# ACS712.net
KiCad netlist of a schematic drawn in Altium Designer
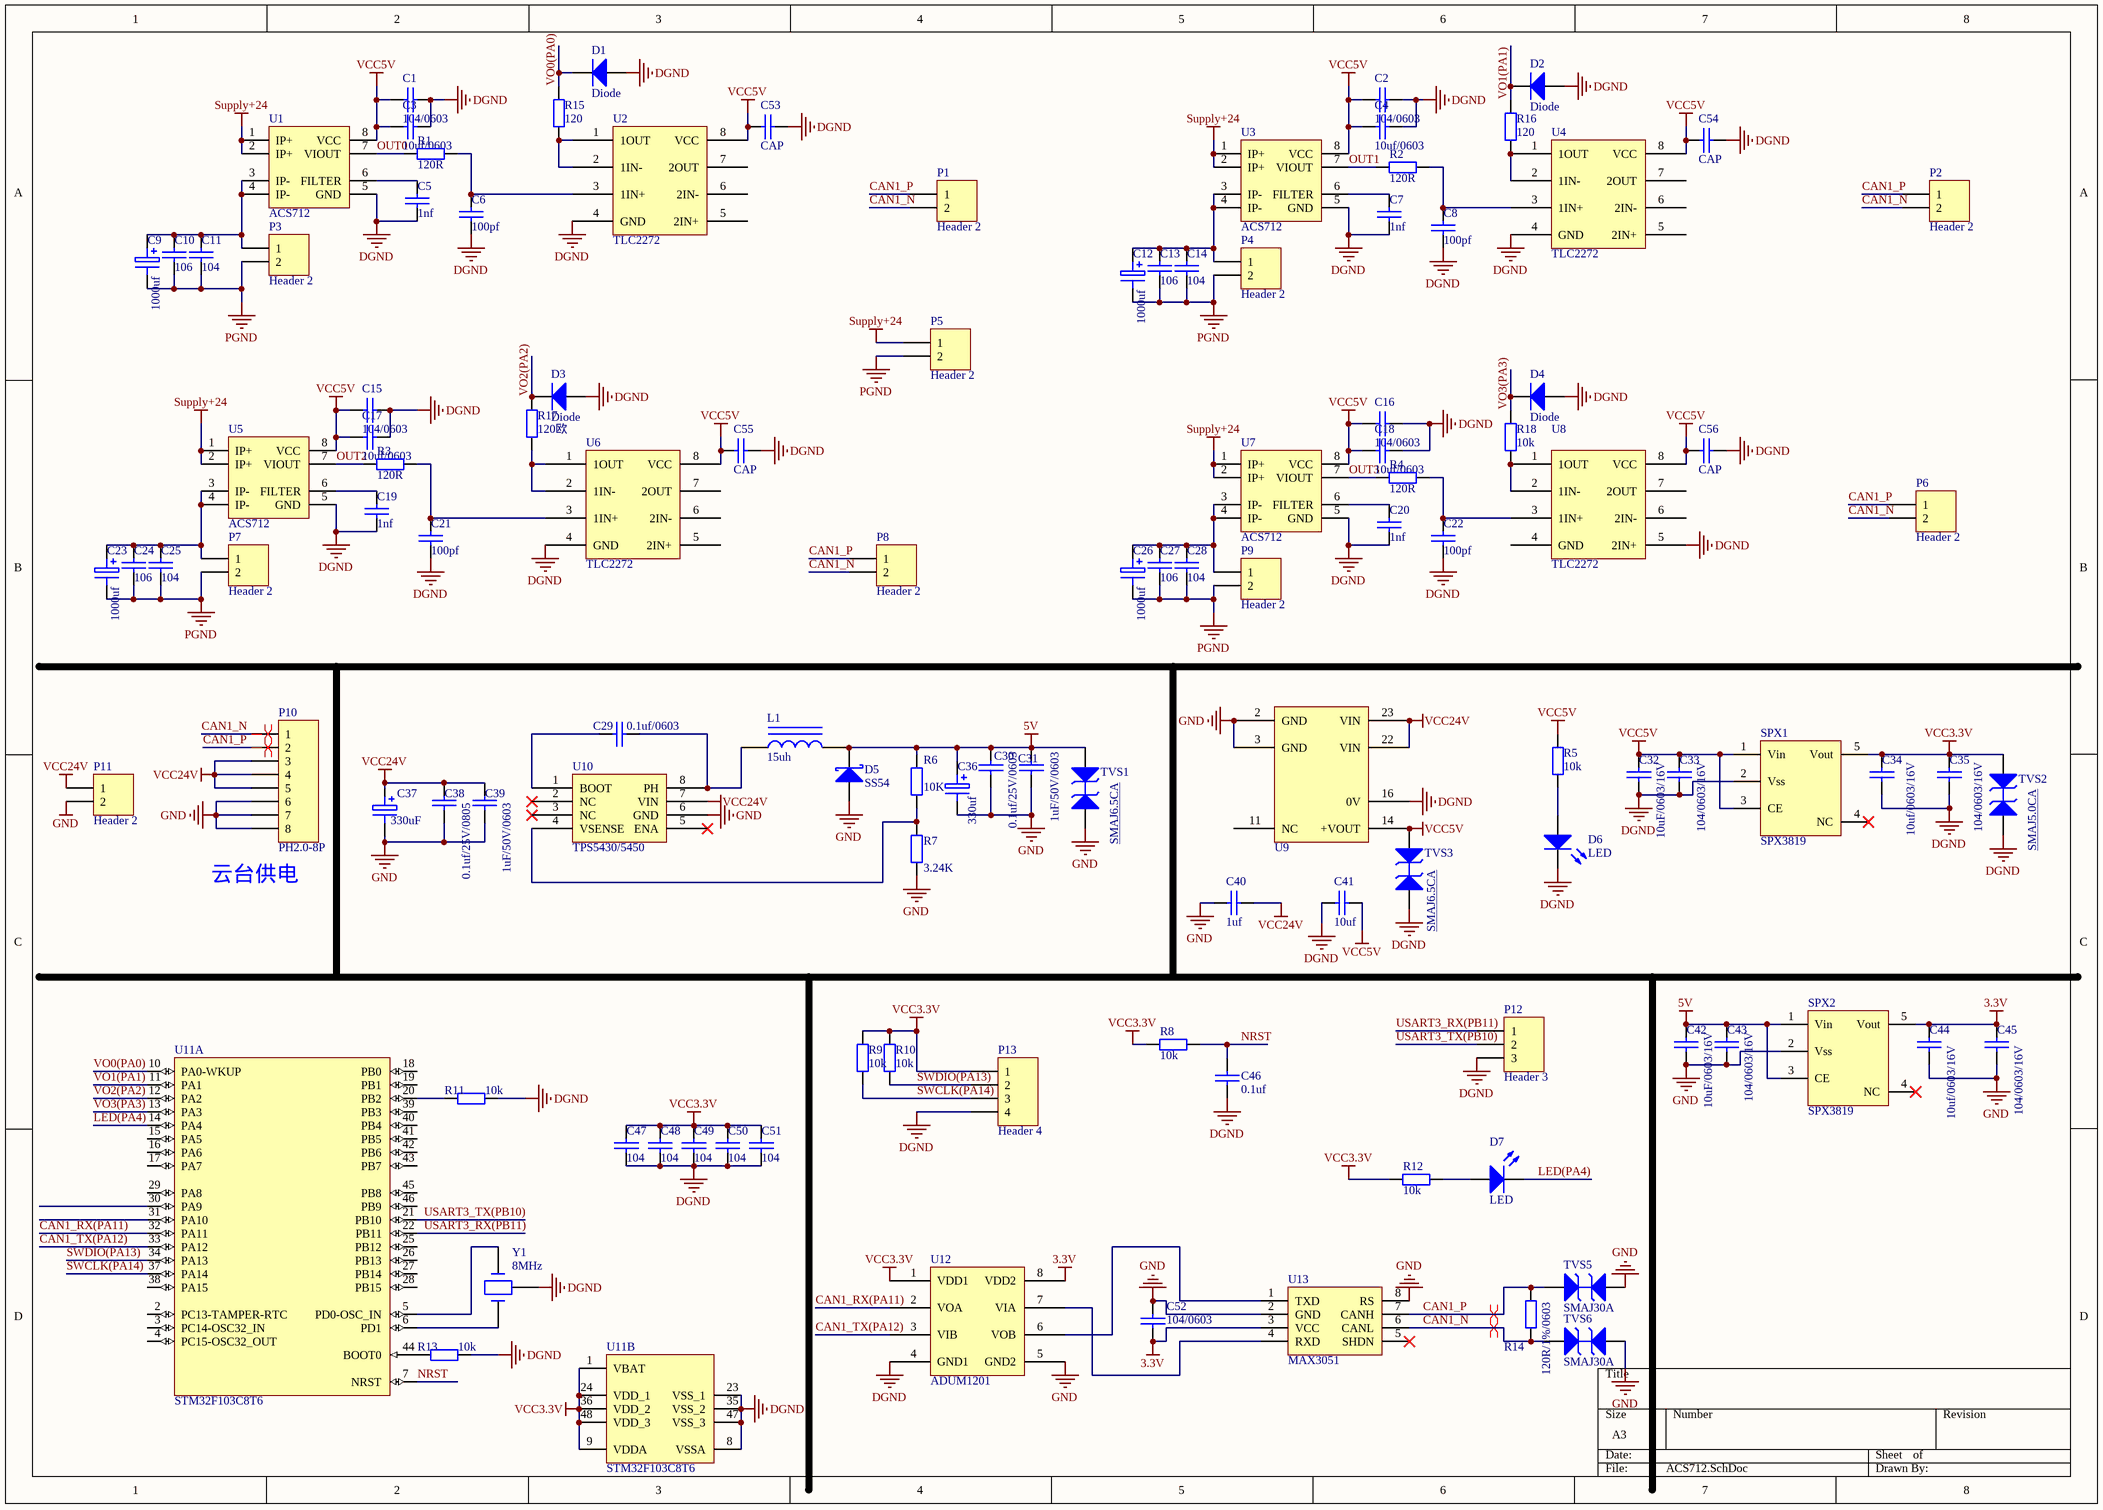
[diagram p0: ACS712.SchDoc]

(export (version "E")
  (design (tool "Eeschema 10.0.6"))
  (components
    (comp (ref "C1") (value "104/0603") (footprint "C0603") (libsource (lib "Common Device") (part "CAP")))
    (comp (ref "C2") (value "104/0603") (footprint "C0603") (libsource (lib "Common Device") (part "CAP")))
    (comp (ref "C3") (value "10uf/0603") (footprint "C0603") (libsource (lib "Common Device") (part "CAP")))
    (comp (ref "C4") (value "10uf/0603") (footprint "C0603") (libsource (lib "Common Device") (part "CAP")))
    (comp (ref "C5") (value "1nf") (footprint "C0603") (libsource (lib "Common Device") (part "CAP")))
    (comp (ref "C6") (value "100pf") (footprint "C0603") (libsource (lib "Common Device") (part "CAP")))
    (comp (ref "C7") (value "1nf") (footprint "C0603") (libsource (lib "Common Device") (part "CAP")))
    (comp (ref "C8") (value "100pf") (footprint "C0603") (libsource (lib "Common Device") (part "CAP")))
    (comp (ref "C9") (value "1000uf") (footprint "C13x20") (libsource (lib "Common Device") (part "CAP POL")))
    (comp (ref "C10") (value "106") (footprint "C0603") (libsource (lib "Common Device") (part "CAP")))
    (comp (ref "C11") (value "104") (footprint "C0603") (libsource (lib "Common Device") (part "CAP")))
    (comp (ref "C12")
      (value "1000uf")
      (footprint "C13x20")
      (libsource (lib "Common Device") (part "CAP POL"))
    )
    (comp (ref "C13") (value "106") (footprint "C0603") (libsource (lib "Common Device") (part "CAP")))
    (comp (ref "C14") (value "104") (footprint "C0603") (libsource (lib "Common Device") (part "CAP")))
    (comp (ref "C15") (value "104/0603") (footprint "C0603") (libsource (lib "Common Device") (part "CAP")))
    (comp (ref "C16") (value "104/0603") (footprint "C0603") (libsource (lib "Common Device") (part "CAP")))
    (comp (ref "C17") (value "10uf/0603") (footprint "C0603") (libsource (lib "Common Device") (part "CAP")))
    (comp (ref "C18") (value "10uf/0603") (footprint "C0603") (libsource (lib "Common Device") (part "CAP")))
    (comp (ref "C19") (value "1nf") (footprint "C0603") (libsource (lib "Common Device") (part "CAP")))
    (comp (ref "C20") (value "1nf") (footprint "C0603") (libsource (lib "Common Device") (part "CAP")))
    (comp (ref "C21") (value "100pf") (footprint "C0603") (libsource (lib "Common Device") (part "CAP")))
    (comp (ref "C22") (value "100pf") (footprint "C0603") (libsource (lib "Common Device") (part "CAP")))
    (comp (ref "C23")
      (value "1000uf")
      (footprint "C13x20")
      (libsource (lib "Common Device") (part "CAP POL"))
    )
    (comp (ref "C24") (value "106") (footprint "C0603") (libsource (lib "Common Device") (part "CAP")))
    (comp (ref "C25") (value "104") (footprint "C0603") (libsource (lib "Common Device") (part "CAP")))
    (comp (ref "C26")
      (value "1000uf")
      (footprint "C13x20")
      (libsource (lib "Common Device") (part "CAP POL"))
    )
    (comp (ref "C27") (value "106") (footprint "C0603") (libsource (lib "Common Device") (part "CAP")))
    (comp (ref "C28") (value "104") (footprint "C0603") (libsource (lib "Common Device") (part "CAP")))
    (comp (ref "C29") (value "0.1uf/0603") (footprint "C0603") (libsource (lib "Common Device") (part "CAP")))
    (comp (ref "C30")
      (value "0.1uf/25V/0603")
      (footprint "C0603")
      (libsource (lib "Common Device") (part "CAP"))
    )
    (comp (ref "C31")
      (value "1uF/50V/0603")
      (footprint "C0603")
      (libsource (lib "Common Device") (part "CAP"))
    )
    (comp (ref "C32")
      (value "10uF/0603/16V")
      (footprint "C0603")
      (fields (field (name "ALTIUM_UNNAMED_1") "10uF/0603/16V"))
      (libsource (lib "Common Device") (part "CAP"))
    )
    (comp (ref "C33")
      (value "104/0603/16V")
      (footprint "C0603")
      (fields (field (name "ALTIUM_UNNAMED_1") "104/0603/16V"))
      (libsource (lib "Common Device") (part "CAP"))
    )
    (comp (ref "C34")
      (value "104/0603/16V")
      (footprint "C0603")
      (fields (field (name "ALTIUM_UNNAMED_1") "10uf/0603/16V"))
      (libsource (lib "Common Device") (part "CAP"))
    )
    (comp (ref "C35")
      (value "104/0603/16V")
      (footprint "C0603")
      (fields (field (name "ALTIUM_UNNAMED_1") "104/0603/16V"))
      (libsource (lib "Common Device") (part "CAP"))
    )
    (comp (ref "C36") (value "330uf") (footprint "C3528") (libsource (lib "Common Device") (part "CAP POL")))
    (comp (ref "C37") (value "330uF") (footprint "C10x16") (libsource (lib "Common Device") (part "CAP POL")))
    (comp (ref "C38")
      (value "0.1uf/25V/0805")
      (footprint "C0603")
      (libsource (lib "Common Device") (part "CAP"))
    )
    (comp (ref "C39")
      (value "1uF/50V/0603")
      (footprint "C0603")
      (libsource (lib "Common Device") (part "CAP"))
    )
    (comp (ref "C40") (value "1uf") (footprint "C0805") (libsource (lib "Common Device") (part "CAP")))
    (comp (ref "C41") (value "10uf") (footprint "C0805") (libsource (lib "Common Device") (part "CAP")))
    (comp (ref "C42")
      (value "10uF/0603/16V")
      (footprint "C0603")
      (fields (field (name "ALTIUM_UNNAMED_1") "10uF/0603/16V"))
      (libsource (lib "Common Device") (part "CAP"))
    )
    (comp (ref "C43")
      (value "104/0603/16V")
      (footprint "C0603")
      (fields (field (name "ALTIUM_UNNAMED_1") "104/0603/16V"))
      (libsource (lib "Common Device") (part "CAP"))
    )
    (comp (ref "C44")
      (value "104/0603/16V")
      (footprint "C0603")
      (fields (field (name "ALTIUM_UNNAMED_1") "10uf/0603/16V"))
      (libsource (lib "Common Device") (part "CAP"))
    )
    (comp (ref "C45")
      (value "104/0603/16V")
      (footprint "C0603")
      (fields (field (name "ALTIUM_UNNAMED_1") "104/0603/16V"))
      (libsource (lib "Common Device") (part "CAP"))
    )
    (comp (ref "C46") (value "0.1uf") (footprint "C0603") (libsource (lib "Common Device") (part "CAP")))
    (comp (ref "C47") (value "104") (footprint "C0603") (libsource (lib "Common Device") (part "CAP")))
    (comp (ref "C48") (value "104") (footprint "C0603") (libsource (lib "Common Device") (part "CAP")))
    (comp (ref "C49") (value "104") (footprint "C0603") (libsource (lib "Common Device") (part "CAP")))
    (comp (ref "C50") (value "104") (footprint "C0603") (libsource (lib "Common Device") (part "CAP")))
    (comp (ref "C51") (value "104") (footprint "C0603") (libsource (lib "Common Device") (part "CAP")))
    (comp (ref "C52") (value "104/0603") (footprint "C0603") (libsource (lib "Common Device") (part "CAP")))
    (comp (ref "C53") (value "CAP") (footprint "C0603") (libsource (lib "Common Device") (part "CAP")))
    (comp (ref "C54") (value "CAP") (footprint "C0603") (libsource (lib "Common Device") (part "CAP")))
    (comp (ref "C55") (value "CAP") (footprint "C0603") (libsource (lib "Common Device") (part "CAP")))
    (comp (ref "C56") (value "CAP") (footprint "C0603") (libsource (lib "Common Device") (part "CAP")))
    (comp (ref "D1") (value "Diode") (footprint "D1206") (libsource (lib "Common Device") (part "Diode")))
    (comp (ref "D2") (value "Diode") (footprint "D1206") (libsource (lib "Common Device") (part "Diode")))
    (comp (ref "D3") (value "Diode") (footprint "D1206") (libsource (lib "Common Device") (part "Diode")))
    (comp (ref "D4") (value "Diode") (footprint "D1206") (libsource (lib "Common Device") (part "Diode")))
    (comp (ref "D5")
      (value "SS54")
      (footprint "DO-214AA")
      (libsource (lib "Common Device") (part "Diode Schottky"))
    )
    (comp (ref "D6") (value "LED") (footprint "R0603") (libsource (lib "Common Device") (part "LED")))
    (comp (ref "D7") (value "LED") (footprint "R0603") (libsource (lib "Common Device") (part "LED")))
    (comp (ref "L1") (value "15uh") (footprint "L0630") (libsource (lib "Common Device") (part "L电感")))
    (comp (ref "P1")
      (value "Header 2")
      (footprint "GH1.25-2P")
      (description "Header, 2-Pin")
      (fields (field (name "PUBLISHER") "Altium Limited"))
      (libsource (lib "Common Connectors") (part "Header 2"))
    )
    (comp (ref "P2")
      (value "Header 2")
      (footprint "GH1.25-2P")
      (description "Header, 2-Pin")
      (fields (field (name "PUBLISHER") "Altium Limited"))
      (libsource (lib "Common Connectors") (part "Header 2"))
    )
    (comp (ref "P3")
      (value "Header 2")
      (footprint "XT30U-F")
      (description "Header, 2-Pin")
      (fields (field (name "PUBLISHER") "Altium Limited"))
      (libsource (lib "Common Connectors") (part "Header 2"))
    )
    (comp (ref "P4")
      (value "Header 2")
      (footprint "XT30U-F")
      (description "Header, 2-Pin")
      (fields (field (name "PUBLISHER") "Altium Limited"))
      (libsource (lib "Common Connectors") (part "Header 2"))
    )
    (comp (ref "P5")
      (value "Header 2")
      (footprint "XT30U-F")
      (description "Header, 2-Pin")
      (fields (field (name "PUBLISHER") "Altium Limited"))
      (libsource (lib "Common Connectors") (part "Header 2"))
    )
    (comp (ref "P6")
      (value "Header 2")
      (footprint "GH1.25-2P")
      (description "Header, 2-Pin")
      (fields (field (name "PUBLISHER") "Altium Limited"))
      (libsource (lib "Common Connectors") (part "Header 2"))
    )
    (comp (ref "P7")
      (value "Header 2")
      (footprint "XT30U-F")
      (description "Header, 2-Pin")
      (fields (field (name "PUBLISHER") "Altium Limited"))
      (libsource (lib "Common Connectors") (part "Header 2"))
    )
    (comp (ref "P8")
      (value "Header 2")
      (footprint "GH1.25-2P")
      (description "Header, 2-Pin")
      (fields (field (name "PUBLISHER") "Altium Limited"))
      (libsource (lib "Common Connectors") (part "Header 2"))
    )
    (comp (ref "P9")
      (value "Header 2")
      (footprint "XT30U-F")
      (description "Header, 2-Pin")
      (fields (field (name "PUBLISHER") "Altium Limited"))
      (libsource (lib "Common Connectors") (part "Header 2"))
    )
    (comp (ref "P10")
      (value "PH2.0-8P")
      (footprint "PH2.0-8P")
      (description "Header, 8-Pin")
      (fields (field (name "PUBLISHER") "Altium Limited"))
      (libsource (lib "Common Connectors") (part "Header 8"))
    )
    (comp (ref "P11")
      (value "Header 2")
      (footprint "XT30U-F")
      (description "Header, 2-Pin")
      (fields (field (name "PUBLISHER") "Altium Limited"))
      (libsource (lib "Common Connectors") (part "Header 2"))
    )
    (comp (ref "P12")
      (value "Header 3")
      (footprint "GH1.25-3P")
      (description "Header, 3-Pin")
      (fields (field (name "PUBLISHER") "Altium Limited"))
      (libsource (lib "Common Connectors") (part "Header 3"))
    )
    (comp (ref "P13")
      (value "Header 4")
      (footprint "GH1.25-4P")
      (description "Header, 4-Pin")
      (fields (field (name "PUBLISHER") "Altium Limited"))
      (libsource (lib "Common Connectors") (part "Header 4"))
    )
    (comp (ref "R1") (value "120R") (footprint "R0603") (libsource (lib "Common Device") (part "Resistance")))
    (comp (ref "R2") (value "120R") (footprint "R0603") (libsource (lib "Common Device") (part "Resistance")))
    (comp (ref "R3") (value "120R") (footprint "R0603") (libsource (lib "Common Device") (part "Resistance")))
    (comp (ref "R4") (value "120R") (footprint "R0603") (libsource (lib "Common Device") (part "Resistance")))
    (comp (ref "R5") (value "10k") (footprint "R0603") (libsource (lib "") (part "Resistance_1")))
    (comp (ref "R6") (value "10K") (footprint "R0603") (libsource (lib "") (part "Resistance_1")))
    (comp (ref "R7") (value "3.24K") (footprint "R0603") (libsource (lib "") (part "Resistance_1")))
    (comp (ref "R8") (value "10k") (footprint "R0603") (libsource (lib "Common Device") (part "Resistance")))
    (comp (ref "R9") (value "10k") (footprint "R0603") (libsource (lib "") (part "Resistance_1")))
    (comp (ref "R10") (value "10k") (footprint "R0603") (libsource (lib "") (part "Resistance_1")))
    (comp (ref "R11") (value "10k") (footprint "R0603") (libsource (lib "Common Device") (part "Resistance")))
    (comp (ref "R12") (value "10k") (footprint "R0603") (libsource (lib "Common Device") (part "Resistance")))
    (comp (ref "R13") (value "10k") (footprint "R0603") (libsource (lib "Common Device") (part "Resistance")))
    (comp (ref "R14") (value "120R/1%/0603") (footprint "R0603") (libsource (lib "") (part "Resistance_2")))
    (comp (ref "R15") (value "120") (footprint "R0603") (libsource (lib "") (part "Resistance_1")))
    (comp (ref "R16") (value "120") (footprint "R0603") (libsource (lib "") (part "Resistance_1")))
    (comp (ref "R17") (value "120欧") (footprint "R0603") (libsource (lib "") (part "Resistance_2")))
    (comp (ref "R18") (value "10k") (footprint "R0603") (libsource (lib "") (part "Resistance_1")))
    (comp (ref "SPX1")
      (value "SPX3819")
      (footprint "SOT23-5")
      (libsource (lib "Common Power") (part "XC6219"))
    )
    (comp (ref "SPX2")
      (value "SPX3819")
      (footprint "SOT23-5")
      (libsource (lib "Common Power") (part "XC6219"))
    )
    (comp (ref "TVS1")
      (value "SMAJ6.5CA")
      (footprint "DO-214AC")
      (description "SMBJ24CA")
      (libsource (lib "VL53L0X激光测距传感器模块") (part "TVS"))
    )
    (comp (ref "TVS2")
      (value "SMAJ5.0CA")
      (footprint "DO-214AC")
      (description "SMBJ24CA")
      (libsource (lib "VL53L0X激光测距传感器模块") (part "TVS"))
    )
    (comp (ref "TVS3")
      (value "SMAJ6.5CA")
      (footprint "DO-214AC")
      (description "SMBJ24CA")
      (libsource (lib "VL53L0X激光测距传感器模块") (part "TVS"))
    )
    (comp (ref "TVS5")
      (value "SMAJ30A")
      (footprint "DO-214AC")
      (description "SMBJ24CA")
      (libsource (lib "VL53L0X激光测距传感器模块") (part "TVS"))
    )
    (comp (ref "TVS6")
      (value "SMAJ30A")
      (footprint "DO-214AC")
      (libsource (lib "VL53L0X激光测距传感器模块") (part "TVS"))
    )
    (comp (ref "U1") (value "ACS712") (footprint "SOIC-8") (libsource (lib "Common Device") (part "ACS712")))
    (comp (ref "U2")
      (value "TLC2272")
      (footprint "SOIC-8")
      (libsource (lib "Common Device") (part "TLC2272"))
    )
    (comp (ref "U3") (value "ACS712") (footprint "SOIC-8") (libsource (lib "Common Device") (part "ACS712")))
    (comp (ref "U4")
      (value "TLC2272")
      (footprint "SOIC-8")
      (libsource (lib "Common Device") (part "TLC2272"))
    )
    (comp (ref "U5") (value "ACS712") (footprint "SOIC-8") (libsource (lib "Common Device") (part "ACS712")))
    (comp (ref "U6")
      (value "TLC2272")
      (footprint "SOIC-8")
      (libsource (lib "Common Device") (part "TLC2272"))
    )
    (comp (ref "U7") (value "ACS712") (footprint "SOIC-8") (libsource (lib "Common Device") (part "ACS712")))
    (comp (ref "U8")
      (value "TLC2272")
      (footprint "SOIC-8")
      (libsource (lib "Common Device") (part "TLC2272"))
    )
    (comp (ref "U9")
      (value "VRB_ZP-6WR3")
      (footprint "VRB_ZP-6WR3")
      (libsource (lib "Common Device") (part "VRB_ZP-6WR3"))
    )
    (comp (ref "U10")
      (value "TPS5430/5450")
      (footprint "SOIC-8")
      (libsource (lib "Common Power") (part "TPS5430/5450"))
    )
    (comp (ref "U11")
      (value "STM32F103C8T6")
      (footprint "LQFP48_N")
      (libsource (lib "STMicroelectronics STM32 F1") (part "STM32F103C8T6"))
    )
    (comp (ref "U12")
      (value "ADUM1201")
      (footprint "SOIC-8")
      (libsource (lib "Common Device") (part "ADUM1201"))
    )
    (comp (ref "U13")
      (value "MAX3051")
      (footprint "SOT-23-8P")
      (libsource (lib "VL53L0X激光测距传感器模块") (part "MAX3051"))
    )
    (comp (ref "Y1") (value "8MHz") (footprint "CSTCE") (libsource (lib "VL53L0X激光测距传感器模块") (part "CSTCE")))
  )
  (nets
    (net (code "1") (name "/CAN1_N") (class "Default")
      (node (ref "P1") (pin "2") (pinfunction "2_2") (pintype "passive"))
      (node (ref "P10") (pin "1") (pinfunction "1_1") (pintype "passive"))
      (node (ref "P2") (pin "2") (pinfunction "2_2") (pintype "passive"))
      (node (ref "P6") (pin "2") (pinfunction "2_2") (pintype "passive"))
      (node (ref "P8") (pin "2") (pinfunction "2_2") (pintype "passive"))
      (node (ref "R14") (pin "1") (pinfunction "1_1") (pintype "passive"))
      (node (ref "TVS6") (pin "2") (pinfunction "K_2") (pintype "passive"))
      (node (ref "U13") (pin "6") (pinfunction "CANL_6") (pintype "power_in"))
    )
    (net (code "2") (name "/CAN1_P") (class "Default")
      (node (ref "P1") (pin "1") (pinfunction "1_1") (pintype "passive"))
      (node (ref "P10") (pin "2") (pinfunction "2_2") (pintype "passive"))
      (node (ref "P2") (pin "1") (pinfunction "1_1") (pintype "passive"))
      (node (ref "P6") (pin "1") (pinfunction "1_1") (pintype "passive"))
      (node (ref "P8") (pin "1") (pinfunction "1_1") (pintype "passive"))
      (node (ref "R14") (pin "2") (pinfunction "2_2") (pintype "passive"))
      (node (ref "TVS5") (pin "2") (pinfunction "K_2") (pintype "passive"))
      (node (ref "U13") (pin "7") (pinfunction "CANH_7") (pintype "power_in"))
    )
    (net (code "3") (name "/CAN1_RX(PA11)") (class "Default")
      (node (ref "U11") (pin "32") (pinfunction "PA11_32") (pintype "bidirectional"))
      (node (ref "U12") (pin "2") (pinfunction "VOA_2") (pintype "passive"))
    )
    (net (code "4") (name "/CAN1_TX(PA12)") (class "Default")
      (node (ref "U11") (pin "33") (pinfunction "PA12_33") (pintype "bidirectional"))
      (node (ref "U12") (pin "3") (pinfunction "VIB_3") (pintype "passive"))
    )
    (net (code "5") (name "/LED(PA4)") (class "Default")
      (node (ref "D7") (pin "2") (pinfunction "K_2") (pintype "passive"))
      (node (ref "U11") (pin "14") (pinfunction "PA4_14") (pintype "bidirectional"))
    )
    (net (code "6") (name "/NRST") (class "Default")
      (node (ref "C46") (pin "2") (pinfunction "2_2") (pintype "passive"))
      (node (ref "R8") (pin "1") (pinfunction "1_1") (pintype "passive"))
      (node (ref "U11") (pin "7") (pinfunction "NRST_7") (pintype "bidirectional"))
    )
    (net (code "7") (name "/OUT0") (class "Default")
      (node (ref "R1") (pin "2") (pinfunction "2_2") (pintype "passive"))
      (node (ref "U1") (pin "7") (pinfunction "VIOUT_7") (pintype "passive"))
    )
    (net (code "8") (name "/OUT1") (class "Default")
      (node (ref "R2") (pin "2") (pinfunction "2_2") (pintype "passive"))
      (node (ref "U3") (pin "7") (pinfunction "VIOUT_7") (pintype "passive"))
    )
    (net (code "9") (name "/OUT2") (class "Default")
      (node (ref "R3") (pin "2") (pinfunction "2_2") (pintype "passive"))
      (node (ref "U5") (pin "7") (pinfunction "VIOUT_7") (pintype "passive"))
    )
    (net (code "10") (name "/OUT3") (class "Default")
      (node (ref "R4") (pin "2") (pinfunction "2_2") (pintype "passive"))
      (node (ref "U7") (pin "7") (pinfunction "VIOUT_7") (pintype "passive"))
    )
    (net (code "11") (name "/SWCLK(PA14)") (class "Default")
      (node (ref "P13") (pin "3") (pinfunction "3_3") (pintype "passive"))
      (node (ref "R9") (pin "2") (pinfunction "2_2") (pintype "passive"))
      (node (ref "U11") (pin "37") (pinfunction "PA14_37") (pintype "bidirectional"))
    )
    (net (code "12") (name "/SWDIO(PA13)") (class "Default")
      (node (ref "P13") (pin "2") (pinfunction "2_2") (pintype "passive"))
      (node (ref "R10") (pin "2") (pinfunction "2_2") (pintype "passive"))
      (node (ref "U11") (pin "34") (pinfunction "PA13_34") (pintype "bidirectional"))
    )
    (net (code "13") (name "/USART3_RX(PB11)") (class "Default")
      (node (ref "P12") (pin "1") (pinfunction "1_1") (pintype "passive"))
      (node (ref "U11") (pin "22") (pinfunction "PB11_22") (pintype "bidirectional"))
    )
    (net (code "14") (name "/USART3_TX(PB10)") (class "Default")
      (node (ref "P12") (pin "2") (pinfunction "2_2") (pintype "passive"))
      (node (ref "U11") (pin "21") (pinfunction "PB10_21") (pintype "bidirectional"))
    )
    (net (code "15") (name "/VO0(PA0)") (class "Default")
      (node (ref "D1") (pin "2") (pinfunction "K_2") (pintype "passive"))
      (node (ref "R15") (pin "1") (pinfunction "1_1") (pintype "passive"))
      (node (ref "U11") (pin "10") (pinfunction "PA0-WKUP_10") (pintype "bidirectional"))
    )
    (net (code "16") (name "/VO1(PA1)") (class "Default")
      (node (ref "D2") (pin "2") (pinfunction "K_2") (pintype "passive"))
      (node (ref "R16") (pin "1") (pinfunction "1_1") (pintype "passive"))
      (node (ref "U11") (pin "11") (pinfunction "PA1_11") (pintype "bidirectional"))
    )
    (net (code "17") (name "/VO2(PA2)") (class "Default")
      (node (ref "D3") (pin "2") (pinfunction "K_2") (pintype "passive"))
      (node (ref "R17") (pin "2") (pinfunction "2_2") (pintype "passive"))
      (node (ref "U11") (pin "12") (pinfunction "PA2_12") (pintype "bidirectional"))
    )
    (net (code "18") (name "/VO3(PA3)") (class "Default")
      (node (ref "D4") (pin "2") (pinfunction "K_2") (pintype "passive"))
      (node (ref "R18") (pin "1") (pinfunction "1_1") (pintype "passive"))
      (node (ref "U11") (pin "13") (pinfunction "PA3_13") (pintype "bidirectional"))
    )
    (net (code "19") (name "3.3V") (class "Default")
      (node (ref "C44") (pin "2") (pinfunction "2_2") (pintype "passive"))
      (node (ref "C45") (pin "2") (pinfunction "2_2") (pintype "passive"))
      (node (ref "C52") (pin "1") (pinfunction "1_1") (pintype "passive"))
      (node (ref "SPX2") (pin "5") (pinfunction "Vout_5") (pintype "passive"))
      (node (ref "U12") (pin "8") (pinfunction "VDD2_8") (pintype "passive"))
      (node (ref "U13") (pin "3") (pinfunction "VCC_3") (pintype "power_in"))
    )
    (net (code "20") (name "5V") (class "Default")
      (node (ref "C30") (pin "2") (pinfunction "2_2") (pintype "passive"))
      (node (ref "C31") (pin "2") (pinfunction "2_2") (pintype "passive"))
      (node (ref "C36") (pin "1") (pinfunction "1_1") (pintype "passive"))
      (node (ref "C42") (pin "2") (pinfunction "2_2") (pintype "passive"))
      (node (ref "C43") (pin "2") (pinfunction "2_2") (pintype "passive"))
      (node (ref "D5") (pin "2") (pinfunction "K_2") (pintype "passive"))
      (node (ref "L1") (pin "2") (pinfunction "2_2") (pintype "passive"))
      (node (ref "R6") (pin "1") (pinfunction "1_1") (pintype "passive"))
      (node (ref "SPX2") (pin "1") (pinfunction "Vin_1") (pintype "passive"))
      (node (ref "SPX2") (pin "3") (pinfunction "CE_3") (pintype "passive"))
      (node (ref "TVS1") (pin "2") (pinfunction "K_2") (pintype "passive"))
    )
    (net (code "21") (name "DGND") (class "Default")
      (node (ref "C1") (pin "1") (pinfunction "1_1") (pintype "passive"))
      (node (ref "C15") (pin "1") (pinfunction "1_1") (pintype "passive"))
      (node (ref "C16") (pin "1") (pinfunction "1_1") (pintype "passive"))
      (node (ref "C17") (pin "1") (pinfunction "1_1") (pintype "passive"))
      (node (ref "C18") (pin "1") (pinfunction "1_1") (pintype "passive"))
      (node (ref "C19") (pin "1") (pinfunction "1_1") (pintype "passive"))
      (node (ref "C2") (pin "1") (pinfunction "1_1") (pintype "passive"))
      (node (ref "C20") (pin "1") (pinfunction "1_1") (pintype "passive"))
      (node (ref "C21") (pin "1") (pinfunction "1_1") (pintype "passive"))
      (node (ref "C22") (pin "1") (pinfunction "1_1") (pintype "passive"))
      (node (ref "C3") (pin "1") (pinfunction "1_1") (pintype "passive"))
      (node (ref "C32") (pin "1") (pinfunction "1_1") (pintype "passive"))
      (node (ref "C33") (pin "1") (pinfunction "1_1") (pintype "passive"))
      (node (ref "C34") (pin "1") (pinfunction "1_1") (pintype "passive"))
      (node (ref "C35") (pin "1") (pinfunction "1_1") (pintype "passive"))
      (node (ref "C4") (pin "1") (pinfunction "1_1") (pintype "passive"))
      (node (ref "C41") (pin "1") (pinfunction "1_1") (pintype "passive"))
      (node (ref "C46") (pin "1") (pinfunction "1_1") (pintype "passive"))
      (node (ref "C47") (pin "1") (pinfunction "1_1") (pintype "passive"))
      (node (ref "C48") (pin "1") (pinfunction "1_1") (pintype "passive"))
      (node (ref "C49") (pin "1") (pinfunction "1_1") (pintype "passive"))
      (node (ref "C5") (pin "1") (pinfunction "1_1") (pintype "passive"))
      (node (ref "C50") (pin "1") (pinfunction "1_1") (pintype "passive"))
      (node (ref "C51") (pin "1") (pinfunction "1_1") (pintype "passive"))
      (node (ref "C53") (pin "1") (pinfunction "1_1") (pintype "passive"))
      (node (ref "C54") (pin "1") (pinfunction "1_1") (pintype "passive"))
      (node (ref "C55") (pin "1") (pinfunction "1_1") (pintype "passive"))
      (node (ref "C56") (pin "1") (pinfunction "1_1") (pintype "passive"))
      (node (ref "C6") (pin "1") (pinfunction "1_1") (pintype "passive"))
      (node (ref "C7") (pin "1") (pinfunction "1_1") (pintype "passive"))
      (node (ref "C8") (pin "1") (pinfunction "1_1") (pintype "passive"))
      (node (ref "D1") (pin "1") (pinfunction "A_1") (pintype "passive"))
      (node (ref "D2") (pin "1") (pinfunction "A_1") (pintype "passive"))
      (node (ref "D3") (pin "1") (pinfunction "A_1") (pintype "passive"))
      (node (ref "D4") (pin "1") (pinfunction "A_1") (pintype "passive"))
      (node (ref "D6") (pin "2") (pinfunction "K_2") (pintype "passive"))
      (node (ref "P12") (pin "3") (pinfunction "3_3") (pintype "passive"))
      (node (ref "P13") (pin "4") (pinfunction "4_4") (pintype "passive"))
      (node (ref "R11") (pin "1") (pinfunction "1_1") (pintype "passive"))
      (node (ref "R13") (pin "1") (pinfunction "1_1") (pintype "passive"))
      (node (ref "SPX1") (pin "2") (pinfunction "Vss_2") (pintype "passive"))
      (node (ref "TVS2") (pin "1") (pinfunction "A_1") (pintype "passive"))
      (node (ref "TVS3") (pin "2") (pinfunction "K_2") (pintype "passive"))
      (node (ref "U1") (pin "5") (pinfunction "GND_5") (pintype "passive"))
      (node (ref "U11") (pin "23") (pinfunction "VSS_1_23") (pintype "power_in"))
      (node (ref "U11") (pin "35") (pinfunction "VSS_2_35") (pintype "power_in"))
      (node (ref "U11") (pin "47") (pinfunction "VSS_3_47") (pintype "power_in"))
      (node (ref "U11") (pin "8") (pinfunction "VSSA_8") (pintype "power_in"))
      (node (ref "U12") (pin "4") (pinfunction "GND1_4") (pintype "passive"))
      (node (ref "U2") (pin "4") (pinfunction "GND_4") (pintype "passive"))
      (node (ref "U3") (pin "5") (pinfunction "GND_5") (pintype "passive"))
      (node (ref "U4") (pin "4") (pinfunction "GND_4") (pintype "passive"))
      (node (ref "U5") (pin "5") (pinfunction "GND_5") (pintype "passive"))
      (node (ref "U6") (pin "4") (pinfunction "GND_4") (pintype "passive"))
      (node (ref "U7") (pin "5") (pinfunction "GND_5") (pintype "passive"))
      (node (ref "U8") (pin "5") (pinfunction "2IN+_5") (pintype "passive"))
      (node (ref "U9") (pin "16") (pinfunction "0V_16") (pintype "passive"))
      (node (ref "Y1") (pin "3") (pinfunction "OSC3_3") (pintype "passive"))
    )
    (net (code "22") (name "GND") (class "Default")
      (node (ref "C30") (pin "1") (pinfunction "1_1") (pintype "passive"))
      (node (ref "C31") (pin "1") (pinfunction "1_1") (pintype "passive"))
      (node (ref "C36") (pin "2") (pinfunction "E_2") (pintype "passive"))
      (node (ref "C37") (pin "2") (pinfunction "E_2") (pintype "passive"))
      (node (ref "C38") (pin "1") (pinfunction "1_1") (pintype "passive"))
      (node (ref "C39") (pin "1") (pinfunction "1_1") (pintype "passive"))
      (node (ref "C40") (pin "1") (pinfunction "1_1") (pintype "passive"))
      (node (ref "C42") (pin "1") (pinfunction "1_1") (pintype "passive"))
      (node (ref "C43") (pin "1") (pinfunction "1_1") (pintype "passive"))
      (node (ref "C44") (pin "1") (pinfunction "1_1") (pintype "passive"))
      (node (ref "C45") (pin "1") (pinfunction "1_1") (pintype "passive"))
      (node (ref "C52") (pin "2") (pinfunction "2_2") (pintype "passive"))
      (node (ref "D5") (pin "1") (pinfunction "A_1") (pintype "passive"))
      (node (ref "P10") (pin "6") (pinfunction "6_6") (pintype "passive"))
      (node (ref "P10") (pin "7") (pinfunction "7_7") (pintype "passive"))
      (node (ref "P10") (pin "8") (pinfunction "8_8") (pintype "passive"))
      (node (ref "P11") (pin "2") (pinfunction "2_2") (pintype "passive"))
      (node (ref "R7") (pin "2") (pinfunction "2_2") (pintype "passive"))
      (node (ref "SPX2") (pin "2") (pinfunction "Vss_2") (pintype "passive"))
      (node (ref "TVS1") (pin "1") (pinfunction "A_1") (pintype "passive"))
      (node (ref "TVS5") (pin "1") (pinfunction "A_1") (pintype "passive"))
      (node (ref "TVS6") (pin "1") (pinfunction "A_1") (pintype "passive"))
      (node (ref "U10") (pin "6") (pinfunction "GND_6") (pintype "passive"))
      (node (ref "U12") (pin "5") (pinfunction "GND2_5") (pintype "passive"))
      (node (ref "U13") (pin "2") (pinfunction "GND_2") (pintype "power_in"))
      (node (ref "U13") (pin "8") (pinfunction "RS_8") (pintype "power_in"))
      (node (ref "U9") (pin "2") (pinfunction "GND_2") (pintype "passive"))
      (node (ref "U9") (pin "3") (pinfunction "GND_3") (pintype "passive"))
    )
    (net (code "23") (name "Net-(C10-Pad2)") (class "Default")
      (node (ref "C10") (pin "2") (pinfunction "2_2") (pintype "passive"))
      (node (ref "C11") (pin "2") (pinfunction "2_2") (pintype "passive"))
      (node (ref "C9") (pin "1") (pinfunction "1_1") (pintype "passive"))
      (node (ref "P3") (pin "1") (pinfunction "1_1") (pintype "passive"))
      (node (ref "U1") (pin "3") (pinfunction "IP-_3") (pintype "passive"))
      (node (ref "U1") (pin "4") (pinfunction "IP-_4") (pintype "passive"))
    )
    (net (code "24") (name "Net-(C12-Pad1)") (class "Default")
      (node (ref "C12") (pin "1") (pinfunction "1_1") (pintype "passive"))
      (node (ref "C13") (pin "2") (pinfunction "2_2") (pintype "passive"))
      (node (ref "C14") (pin "2") (pinfunction "2_2") (pintype "passive"))
      (node (ref "P4") (pin "1") (pinfunction "1_1") (pintype "passive"))
      (node (ref "U3") (pin "3") (pinfunction "IP-_3") (pintype "passive"))
      (node (ref "U3") (pin "4") (pinfunction "IP-_4") (pintype "passive"))
    )
    (net (code "25") (name "Net-(C23-Pad1)") (class "Default")
      (node (ref "C23") (pin "1") (pinfunction "1_1") (pintype "passive"))
      (node (ref "C24") (pin "2") (pinfunction "2_2") (pintype "passive"))
      (node (ref "C25") (pin "2") (pinfunction "2_2") (pintype "passive"))
      (node (ref "P7") (pin "1") (pinfunction "1_1") (pintype "passive"))
      (node (ref "U5") (pin "3") (pinfunction "IP-_3") (pintype "passive"))
      (node (ref "U5") (pin "4") (pinfunction "IP-_4") (pintype "passive"))
    )
    (net (code "26") (name "Net-(C26-Pad1)") (class "Default")
      (node (ref "C26") (pin "1") (pinfunction "1_1") (pintype "passive"))
      (node (ref "C27") (pin "2") (pinfunction "2_2") (pintype "passive"))
      (node (ref "C28") (pin "2") (pinfunction "2_2") (pintype "passive"))
      (node (ref "P9") (pin "1") (pinfunction "1_1") (pintype "passive"))
      (node (ref "U7") (pin "3") (pinfunction "IP-_3") (pintype "passive"))
      (node (ref "U7") (pin "4") (pinfunction "IP-_4") (pintype "passive"))
    )
    (net (code "27") (name "Net-(D6-A)") (class "Default")
      (node (ref "D6") (pin "1") (pinfunction "A_1") (pintype "passive"))
      (node (ref "R5") (pin "2") (pinfunction "2_2") (pintype "passive"))
    )
    (net (code "28") (name "Net-(D7-A)") (class "Default")
      (node (ref "D7") (pin "1") (pinfunction "A_1") (pintype "passive"))
      (node (ref "R12") (pin "1") (pinfunction "1_1") (pintype "passive"))
    )
    (net (code "29") (name "Net-(U1-FILTER)") (class "Default")
      (node (ref "C5") (pin "2") (pinfunction "2_2") (pintype "passive"))
      (node (ref "U1") (pin "6") (pinfunction "FILTER_6") (pintype "passive"))
    )
    (net (code "30") (name "Net-(U2-1IN+)") (class "Default")
      (node (ref "C6") (pin "2") (pinfunction "2_2") (pintype "passive"))
      (node (ref "R1") (pin "1") (pinfunction "1_1") (pintype "passive"))
      (node (ref "U2") (pin "3") (pinfunction "1IN+_3") (pintype "passive"))
    )
    (net (code "31") (name "Net-(U2-1IN-)") (class "Default")
      (node (ref "R15") (pin "2") (pinfunction "2_2") (pintype "passive"))
      (node (ref "U2") (pin "1") (pinfunction "1OUT_1") (pintype "passive"))
      (node (ref "U2") (pin "2") (pinfunction "1IN-_2") (pintype "passive"))
    )
    (net (code "32") (name "Net-(U3-FILTER)") (class "Default")
      (node (ref "C7") (pin "2") (pinfunction "2_2") (pintype "passive"))
      (node (ref "U3") (pin "6") (pinfunction "FILTER_6") (pintype "passive"))
    )
    (net (code "33") (name "Net-(U4-1IN+)") (class "Default")
      (node (ref "C8") (pin "2") (pinfunction "2_2") (pintype "passive"))
      (node (ref "R2") (pin "1") (pinfunction "1_1") (pintype "passive"))
      (node (ref "U4") (pin "3") (pinfunction "1IN+_3") (pintype "passive"))
    )
    (net (code "34") (name "Net-(U4-1IN-)") (class "Default")
      (node (ref "R16") (pin "2") (pinfunction "2_2") (pintype "passive"))
      (node (ref "U4") (pin "1") (pinfunction "1OUT_1") (pintype "passive"))
      (node (ref "U4") (pin "2") (pinfunction "1IN-_2") (pintype "passive"))
    )
    (net (code "35") (name "Net-(U5-FILTER)") (class "Default")
      (node (ref "C19") (pin "2") (pinfunction "2_2") (pintype "passive"))
      (node (ref "U5") (pin "6") (pinfunction "FILTER_6") (pintype "passive"))
    )
    (net (code "36") (name "Net-(U6-1IN+)") (class "Default")
      (node (ref "C21") (pin "2") (pinfunction "2_2") (pintype "passive"))
      (node (ref "R3") (pin "1") (pinfunction "1_1") (pintype "passive"))
      (node (ref "U6") (pin "3") (pinfunction "1IN+_3") (pintype "passive"))
    )
    (net (code "37") (name "Net-(U6-1IN-)") (class "Default")
      (node (ref "R17") (pin "1") (pinfunction "1_1") (pintype "passive"))
      (node (ref "U6") (pin "1") (pinfunction "1OUT_1") (pintype "passive"))
      (node (ref "U6") (pin "2") (pinfunction "1IN-_2") (pintype "passive"))
    )
    (net (code "38") (name "Net-(U7-FILTER)") (class "Default")
      (node (ref "C20") (pin "2") (pinfunction "2_2") (pintype "passive"))
      (node (ref "U7") (pin "6") (pinfunction "FILTER_6") (pintype "passive"))
    )
    (net (code "39") (name "Net-(U8-1IN+)") (class "Default")
      (node (ref "C22") (pin "2") (pinfunction "2_2") (pintype "passive"))
      (node (ref "R4") (pin "1") (pinfunction "1_1") (pintype "passive"))
      (node (ref "U8") (pin "3") (pinfunction "1IN+_3") (pintype "passive"))
    )
    (net (code "40") (name "Net-(U8-1IN-)") (class "Default")
      (node (ref "R18") (pin "2") (pinfunction "2_2") (pintype "passive"))
      (node (ref "U8") (pin "1") (pinfunction "1OUT_1") (pintype "passive"))
      (node (ref "U8") (pin "2") (pinfunction "1IN-_2") (pintype "passive"))
    )
    (net (code "41") (name "Net-(U10-BOOT)") (class "Default")
      (node (ref "C29") (pin "2") (pinfunction "2_2") (pintype "passive"))
      (node (ref "U10") (pin "1") (pinfunction "BOOT_1") (pintype "passive"))
    )
    (net (code "42") (name "Net-(U10-PH)") (class "Default")
      (node (ref "C29") (pin "1") (pinfunction "1_1") (pintype "passive"))
      (node (ref "L1") (pin "1") (pinfunction "1_1") (pintype "passive"))
      (node (ref "U10") (pin "8") (pinfunction "PH_8") (pintype "passive"))
    )
    (net (code "43") (name "Net-(U10-VSENSE)") (class "Default")
      (node (ref "R6") (pin "2") (pinfunction "2_2") (pintype "passive"))
      (node (ref "R7") (pin "1") (pinfunction "1_1") (pintype "passive"))
      (node (ref "U10") (pin "4") (pinfunction "VSENSE_4") (pintype "passive"))
    )
    (net (code "44") (name "Net-(U11A-BOOT0)") (class "Default")
      (node (ref "R13") (pin "2") (pinfunction "2_2") (pintype "passive"))
      (node (ref "U11") (pin "44") (pinfunction "BOOT0_44") (pintype "input"))
    )
    (net (code "45") (name "Net-(U11A-PB2)") (class "Default")
      (node (ref "R11") (pin "2") (pinfunction "2_2") (pintype "passive"))
      (node (ref "U11") (pin "20") (pinfunction "PB2_20") (pintype "bidirectional"))
    )
    (net (code "46") (name "Net-(U11A-PD0-OSC_IN)") (class "Default")
      (node (ref "U11") (pin "5") (pinfunction "PD0-OSC_IN_5") (pintype "bidirectional"))
      (node (ref "Y1") (pin "1") (pinfunction "OSC1_1") (pintype "passive"))
    )
    (net (code "47") (name "Net-(U11A-PD1)") (class "Default")
      (node (ref "U11") (pin "6") (pinfunction "PD1_6") (pintype "bidirectional"))
      (node (ref "Y1") (pin "2") (pinfunction "OSC2_2") (pintype "passive"))
    )
    (net (code "48") (name "Net-(U12-VIA)") (class "Default")
      (node (ref "U12") (pin "7") (pinfunction "VIA_7") (pintype "passive"))
      (node (ref "U13") (pin "4") (pinfunction "RXD_4") (pintype "power_in"))
    )
    (net (code "49") (name "Net-(U12-VOB)") (class "Default")
      (node (ref "U12") (pin "6") (pinfunction "VOB_6") (pintype "passive"))
      (node (ref "U13") (pin "1") (pinfunction "TXD_1") (pintype "power_in"))
    )
    (net (code "50") (name "PGND") (class "Default")
      (node (ref "C10") (pin "1") (pinfunction "1_1") (pintype "passive"))
      (node (ref "C11") (pin "1") (pinfunction "1_1") (pintype "passive"))
      (node (ref "C12") (pin "2") (pinfunction "E_2") (pintype "passive"))
      (node (ref "C13") (pin "1") (pinfunction "1_1") (pintype "passive"))
      (node (ref "C14") (pin "1") (pinfunction "1_1") (pintype "passive"))
      (node (ref "C23") (pin "2") (pinfunction "E_2") (pintype "passive"))
      (node (ref "C24") (pin "1") (pinfunction "1_1") (pintype "passive"))
      (node (ref "C25") (pin "1") (pinfunction "1_1") (pintype "passive"))
      (node (ref "C26") (pin "2") (pinfunction "E_2") (pintype "passive"))
      (node (ref "C27") (pin "1") (pinfunction "1_1") (pintype "passive"))
      (node (ref "C28") (pin "1") (pinfunction "1_1") (pintype "passive"))
      (node (ref "C9") (pin "2") (pinfunction "E_2") (pintype "passive"))
      (node (ref "P3") (pin "2") (pinfunction "2_2") (pintype "passive"))
      (node (ref "P4") (pin "2") (pinfunction "2_2") (pintype "passive"))
      (node (ref "P5") (pin "2") (pinfunction "2_2") (pintype "passive"))
      (node (ref "P7") (pin "2") (pinfunction "2_2") (pintype "passive"))
      (node (ref "P9") (pin "2") (pinfunction "2_2") (pintype "passive"))
    )
    (net (code "51") (name "Supply+24") (class "Default")
      (node (ref "P5") (pin "1") (pinfunction "1_1") (pintype "passive"))
      (node (ref "U1") (pin "1") (pinfunction "IP+_1") (pintype "passive"))
      (node (ref "U1") (pin "2") (pinfunction "IP+_2") (pintype "passive"))
      (node (ref "U3") (pin "1") (pinfunction "IP+_1") (pintype "passive"))
      (node (ref "U3") (pin "2") (pinfunction "IP+_2") (pintype "passive"))
      (node (ref "U5") (pin "1") (pinfunction "IP+_1") (pintype "passive"))
      (node (ref "U5") (pin "2") (pinfunction "IP+_2") (pintype "passive"))
      (node (ref "U7") (pin "1") (pinfunction "IP+_1") (pintype "passive"))
      (node (ref "U7") (pin "2") (pinfunction "IP+_2") (pintype "passive"))
    )
    (net (code "52") (name "VCC3.3V") (class "Default")
      (node (ref "C34") (pin "2") (pinfunction "2_2") (pintype "passive"))
      (node (ref "C35") (pin "2") (pinfunction "2_2") (pintype "passive"))
      (node (ref "C47") (pin "2") (pinfunction "2_2") (pintype "passive"))
      (node (ref "C48") (pin "2") (pinfunction "2_2") (pintype "passive"))
      (node (ref "C49") (pin "2") (pinfunction "2_2") (pintype "passive"))
      (node (ref "C50") (pin "2") (pinfunction "2_2") (pintype "passive"))
      (node (ref "C51") (pin "2") (pinfunction "2_2") (pintype "passive"))
      (node (ref "P13") (pin "1") (pinfunction "1_1") (pintype "passive"))
      (node (ref "R10") (pin "1") (pinfunction "1_1") (pintype "passive"))
      (node (ref "R12") (pin "2") (pinfunction "2_2") (pintype "passive"))
      (node (ref "R8") (pin "2") (pinfunction "2_2") (pintype "passive"))
      (node (ref "R9") (pin "1") (pinfunction "1_1") (pintype "passive"))
      (node (ref "SPX1") (pin "5") (pinfunction "Vout_5") (pintype "passive"))
      (node (ref "TVS2") (pin "2") (pinfunction "K_2") (pintype "passive"))
      (node (ref "U11") (pin "1") (pinfunction "VBAT_1") (pintype "power_in"))
      (node (ref "U11") (pin "24") (pinfunction "VDD_1_24") (pintype "power_in"))
      (node (ref "U11") (pin "36") (pinfunction "VDD_2_36") (pintype "power_in"))
      (node (ref "U11") (pin "48") (pinfunction "VDD_3_48") (pintype "power_in"))
      (node (ref "U11") (pin "9") (pinfunction "VDDA_9") (pintype "power_in"))
      (node (ref "U12") (pin "1") (pinfunction "VDD1_1") (pintype "passive"))
    )
    (net (code "53") (name "VCC5V") (class "Default")
      (node (ref "C1") (pin "2") (pinfunction "2_2") (pintype "passive"))
      (node (ref "C15") (pin "2") (pinfunction "2_2") (pintype "passive"))
      (node (ref "C16") (pin "2") (pinfunction "2_2") (pintype "passive"))
      (node (ref "C17") (pin "2") (pinfunction "2_2") (pintype "passive"))
      (node (ref "C18") (pin "2") (pinfunction "2_2") (pintype "passive"))
      (node (ref "C2") (pin "2") (pinfunction "2_2") (pintype "passive"))
      (node (ref "C3") (pin "2") (pinfunction "2_2") (pintype "passive"))
      (node (ref "C32") (pin "2") (pinfunction "2_2") (pintype "passive"))
      (node (ref "C33") (pin "2") (pinfunction "2_2") (pintype "passive"))
      (node (ref "C4") (pin "2") (pinfunction "2_2") (pintype "passive"))
      (node (ref "C41") (pin "2") (pinfunction "2_2") (pintype "passive"))
      (node (ref "C53") (pin "2") (pinfunction "2_2") (pintype "passive"))
      (node (ref "C54") (pin "2") (pinfunction "2_2") (pintype "passive"))
      (node (ref "C55") (pin "2") (pinfunction "2_2") (pintype "passive"))
      (node (ref "C56") (pin "2") (pinfunction "2_2") (pintype "passive"))
      (node (ref "R5") (pin "1") (pinfunction "1_1") (pintype "passive"))
      (node (ref "SPX1") (pin "1") (pinfunction "Vin_1") (pintype "passive"))
      (node (ref "SPX1") (pin "3") (pinfunction "CE_3") (pintype "passive"))
      (node (ref "TVS3") (pin "1") (pinfunction "A_1") (pintype "passive"))
      (node (ref "U1") (pin "8") (pinfunction "VCC_8") (pintype "passive"))
      (node (ref "U2") (pin "8") (pinfunction "VCC_8") (pintype "passive"))
      (node (ref "U3") (pin "8") (pinfunction "VCC_8") (pintype "passive"))
      (node (ref "U4") (pin "8") (pinfunction "VCC_8") (pintype "passive"))
      (node (ref "U5") (pin "8") (pinfunction "VCC_8") (pintype "passive"))
      (node (ref "U6") (pin "8") (pinfunction "VCC_8") (pintype "passive"))
      (node (ref "U7") (pin "8") (pinfunction "VCC_8") (pintype "passive"))
      (node (ref "U8") (pin "8") (pinfunction "VCC_8") (pintype "passive"))
      (node (ref "U9") (pin "14") (pinfunction "+VOUT_14") (pintype "passive"))
    )
    (net (code "54") (name "VCC24V") (class "Default")
      (node (ref "C37") (pin "1") (pinfunction "1_1") (pintype "passive"))
      (node (ref "C38") (pin "2") (pinfunction "2_2") (pintype "passive"))
      (node (ref "C39") (pin "2") (pinfunction "2_2") (pintype "passive"))
      (node (ref "C40") (pin "2") (pinfunction "2_2") (pintype "passive"))
      (node (ref "P10") (pin "3") (pinfunction "3_3") (pintype "passive"))
      (node (ref "P10") (pin "4") (pinfunction "4_4") (pintype "passive"))
      (node (ref "P10") (pin "5") (pinfunction "5_5") (pintype "passive"))
      (node (ref "P11") (pin "1") (pinfunction "1_1") (pintype "passive"))
      (node (ref "U10") (pin "7") (pinfunction "VIN_7") (pintype "passive"))
      (node (ref "U9") (pin "22") (pinfunction "VIN_22") (pintype "passive"))
      (node (ref "U9") (pin "23") (pinfunction "VIN_23") (pintype "passive"))
    )
    (net (code "55") (name "unconnected-(SPX1-NC-Pad4)") (class "Default")
      (node (ref "SPX1") (pin "4") (pinfunction "NC_4") (pintype "passive+no_connect"))
    )
    (net (code "56") (name "unconnected-(SPX2-NC-Pad4)") (class "Default")
      (node (ref "SPX2") (pin "4") (pinfunction "NC_4") (pintype "passive+no_connect"))
    )
    (net (code "57") (name "unconnected-(U2-2IN+-Pad5)") (class "Default")
      (node (ref "U2") (pin "5") (pinfunction "2IN+_5") (pintype "passive"))
    )
    (net (code "58") (name "unconnected-(U2-2IN--Pad6)") (class "Default")
      (node (ref "U2") (pin "6") (pinfunction "2IN-_6") (pintype "passive"))
    )
    (net (code "59") (name "unconnected-(U2-2OUT-Pad7)") (class "Default")
      (node (ref "U2") (pin "7") (pinfunction "2OUT_7") (pintype "passive"))
    )
    (net (code "60") (name "unconnected-(U4-2IN+-Pad5)") (class "Default")
      (node (ref "U4") (pin "5") (pinfunction "2IN+_5") (pintype "passive"))
    )
    (net (code "61") (name "unconnected-(U4-2IN--Pad6)") (class "Default")
      (node (ref "U4") (pin "6") (pinfunction "2IN-_6") (pintype "passive"))
    )
    (net (code "62") (name "unconnected-(U4-2OUT-Pad7)") (class "Default")
      (node (ref "U4") (pin "7") (pinfunction "2OUT_7") (pintype "passive"))
    )
    (net (code "63") (name "unconnected-(U6-2IN+-Pad5)") (class "Default")
      (node (ref "U6") (pin "5") (pinfunction "2IN+_5") (pintype "passive"))
    )
    (net (code "64") (name "unconnected-(U6-2IN--Pad6)") (class "Default")
      (node (ref "U6") (pin "6") (pinfunction "2IN-_6") (pintype "passive"))
    )
    (net (code "65") (name "unconnected-(U6-2OUT-Pad7)") (class "Default")
      (node (ref "U6") (pin "7") (pinfunction "2OUT_7") (pintype "passive"))
    )
    (net (code "66") (name "unconnected-(U8-2IN--Pad6)") (class "Default")
      (node (ref "U8") (pin "6") (pinfunction "2IN-_6") (pintype "passive"))
    )
    (net (code "67") (name "unconnected-(U8-2OUT-Pad7)") (class "Default")
      (node (ref "U8") (pin "7") (pinfunction "2OUT_7") (pintype "passive"))
    )
    (net (code "68") (name "unconnected-(U8-GND-Pad4)") (class "Default")
      (node (ref "U8") (pin "4") (pinfunction "GND_4") (pintype "passive"))
    )
    (net (code "69") (name "unconnected-(U9-NC-Pad11)") (class "Default")
      (node (ref "U9") (pin "11") (pinfunction "NC_11") (pintype "passive"))
    )
    (net (code "70") (name "unconnected-(U10-ENA-Pad5)") (class "Default")
      (node (ref "U10") (pin "5") (pinfunction "ENA_5") (pintype "passive+no_connect"))
    )
    (net (code "71") (name "unconnected-(U10-NC-Pad2)") (class "Default")
      (node (ref "U10") (pin "2") (pinfunction "NC_2") (pintype "passive+no_connect"))
    )
    (net (code "72") (name "unconnected-(U10-NC-Pad3)") (class "Default")
      (node (ref "U10") (pin "3") (pinfunction "NC_3") (pintype "passive+no_connect"))
    )
    (net (code "73") (name "unconnected-(U11A-PA5-Pad15)") (class "Default")
      (node (ref "U11") (pin "15") (pinfunction "PA5_15") (pintype "bidirectional"))
    )
    (net (code "74") (name "unconnected-(U11A-PA6-Pad16)") (class "Default")
      (node (ref "U11") (pin "16") (pinfunction "PA6_16") (pintype "bidirectional"))
    )
    (net (code "75") (name "unconnected-(U11A-PA7-Pad17)") (class "Default")
      (node (ref "U11") (pin "17") (pinfunction "PA7_17") (pintype "bidirectional"))
    )
    (net (code "76") (name "unconnected-(U11A-PA8-Pad29)") (class "Default")
      (node (ref "U11") (pin "29") (pinfunction "PA8_29") (pintype "bidirectional"))
    )
    (net (code "77") (name "unconnected-(U11A-PA9-Pad30)") (class "Default")
      (node (ref "U11") (pin "30") (pinfunction "PA9_30") (pintype "bidirectional"))
    )
    (net (code "78") (name "unconnected-(U11A-PA10-Pad31)") (class "Default")
      (node (ref "U11") (pin "31") (pinfunction "PA10_31") (pintype "bidirectional"))
    )
    (net (code "79") (name "unconnected-(U11A-PA15-Pad38)") (class "Default")
      (node (ref "U11") (pin "38") (pinfunction "PA15_38") (pintype "bidirectional"))
    )
    (net (code "80") (name "unconnected-(U11A-PB0-Pad18)") (class "Default")
      (node (ref "U11") (pin "18") (pinfunction "PB0_18") (pintype "bidirectional"))
    )
    (net (code "81") (name "unconnected-(U11A-PB1-Pad19)") (class "Default")
      (node (ref "U11") (pin "19") (pinfunction "PB1_19") (pintype "bidirectional"))
    )
    (net (code "82") (name "unconnected-(U11A-PB3-Pad39)") (class "Default")
      (node (ref "U11") (pin "39") (pinfunction "PB3_39") (pintype "bidirectional"))
    )
    (net (code "83") (name "unconnected-(U11A-PB4-Pad40)") (class "Default")
      (node (ref "U11") (pin "40") (pinfunction "PB4_40") (pintype "bidirectional"))
    )
    (net (code "84") (name "unconnected-(U11A-PB5-Pad41)") (class "Default")
      (node (ref "U11") (pin "41") (pinfunction "PB5_41") (pintype "bidirectional"))
    )
    (net (code "85") (name "unconnected-(U11A-PB6-Pad42)") (class "Default")
      (node (ref "U11") (pin "42") (pinfunction "PB6_42") (pintype "bidirectional"))
    )
    (net (code "86") (name "unconnected-(U11A-PB7-Pad43)") (class "Default")
      (node (ref "U11") (pin "43") (pinfunction "PB7_43") (pintype "bidirectional"))
    )
    (net (code "87") (name "unconnected-(U11A-PB8-Pad45)") (class "Default")
      (node (ref "U11") (pin "45") (pinfunction "PB8_45") (pintype "bidirectional"))
    )
    (net (code "88") (name "unconnected-(U11A-PB9-Pad46)") (class "Default")
      (node (ref "U11") (pin "46") (pinfunction "PB9_46") (pintype "bidirectional"))
    )
    (net (code "89") (name "unconnected-(U11A-PB12-Pad25)") (class "Default")
      (node (ref "U11") (pin "25") (pinfunction "PB12_25") (pintype "bidirectional"))
    )
    (net (code "90") (name "unconnected-(U11A-PB13-Pad26)") (class "Default")
      (node (ref "U11") (pin "26") (pinfunction "PB13_26") (pintype "bidirectional"))
    )
    (net (code "91") (name "unconnected-(U11A-PB14-Pad27)") (class "Default")
      (node (ref "U11") (pin "27") (pinfunction "PB14_27") (pintype "bidirectional"))
    )
    (net (code "92") (name "unconnected-(U11A-PB15-Pad28)") (class "Default")
      (node (ref "U11") (pin "28") (pinfunction "PB15_28") (pintype "bidirectional"))
    )
    (net (code "93") (name "unconnected-(U11A-PC13-TAMPER-RTC-Pad2)") (class "Default")
      (node (ref "U11") (pin "2") (pinfunction "PC13-TAMPER-RTC_2") (pintype "bidirectional"))
    )
    (net (code "94") (name "unconnected-(U11A-PC14-OSC32_IN-Pad3)") (class "Default")
      (node (ref "U11") (pin "3") (pinfunction "PC14-OSC32_IN_3") (pintype "bidirectional"))
    )
    (net (code "95") (name "unconnected-(U11A-PC15-OSC32_OUT-Pad4)") (class "Default")
      (node (ref "U11") (pin "4") (pinfunction "PC15-OSC32_OUT_4") (pintype "bidirectional"))
    )
    (net (code "96") (name "unconnected-(U13-SHDN-Pad5)") (class "Default")
      (node (ref "U13") (pin "5") (pinfunction "SHDN_5") (pintype "power_in+no_connect"))
    )
  )
)
